# Moisture_Probe.net
KiCad netlist of a schematic drawn in EAGLE
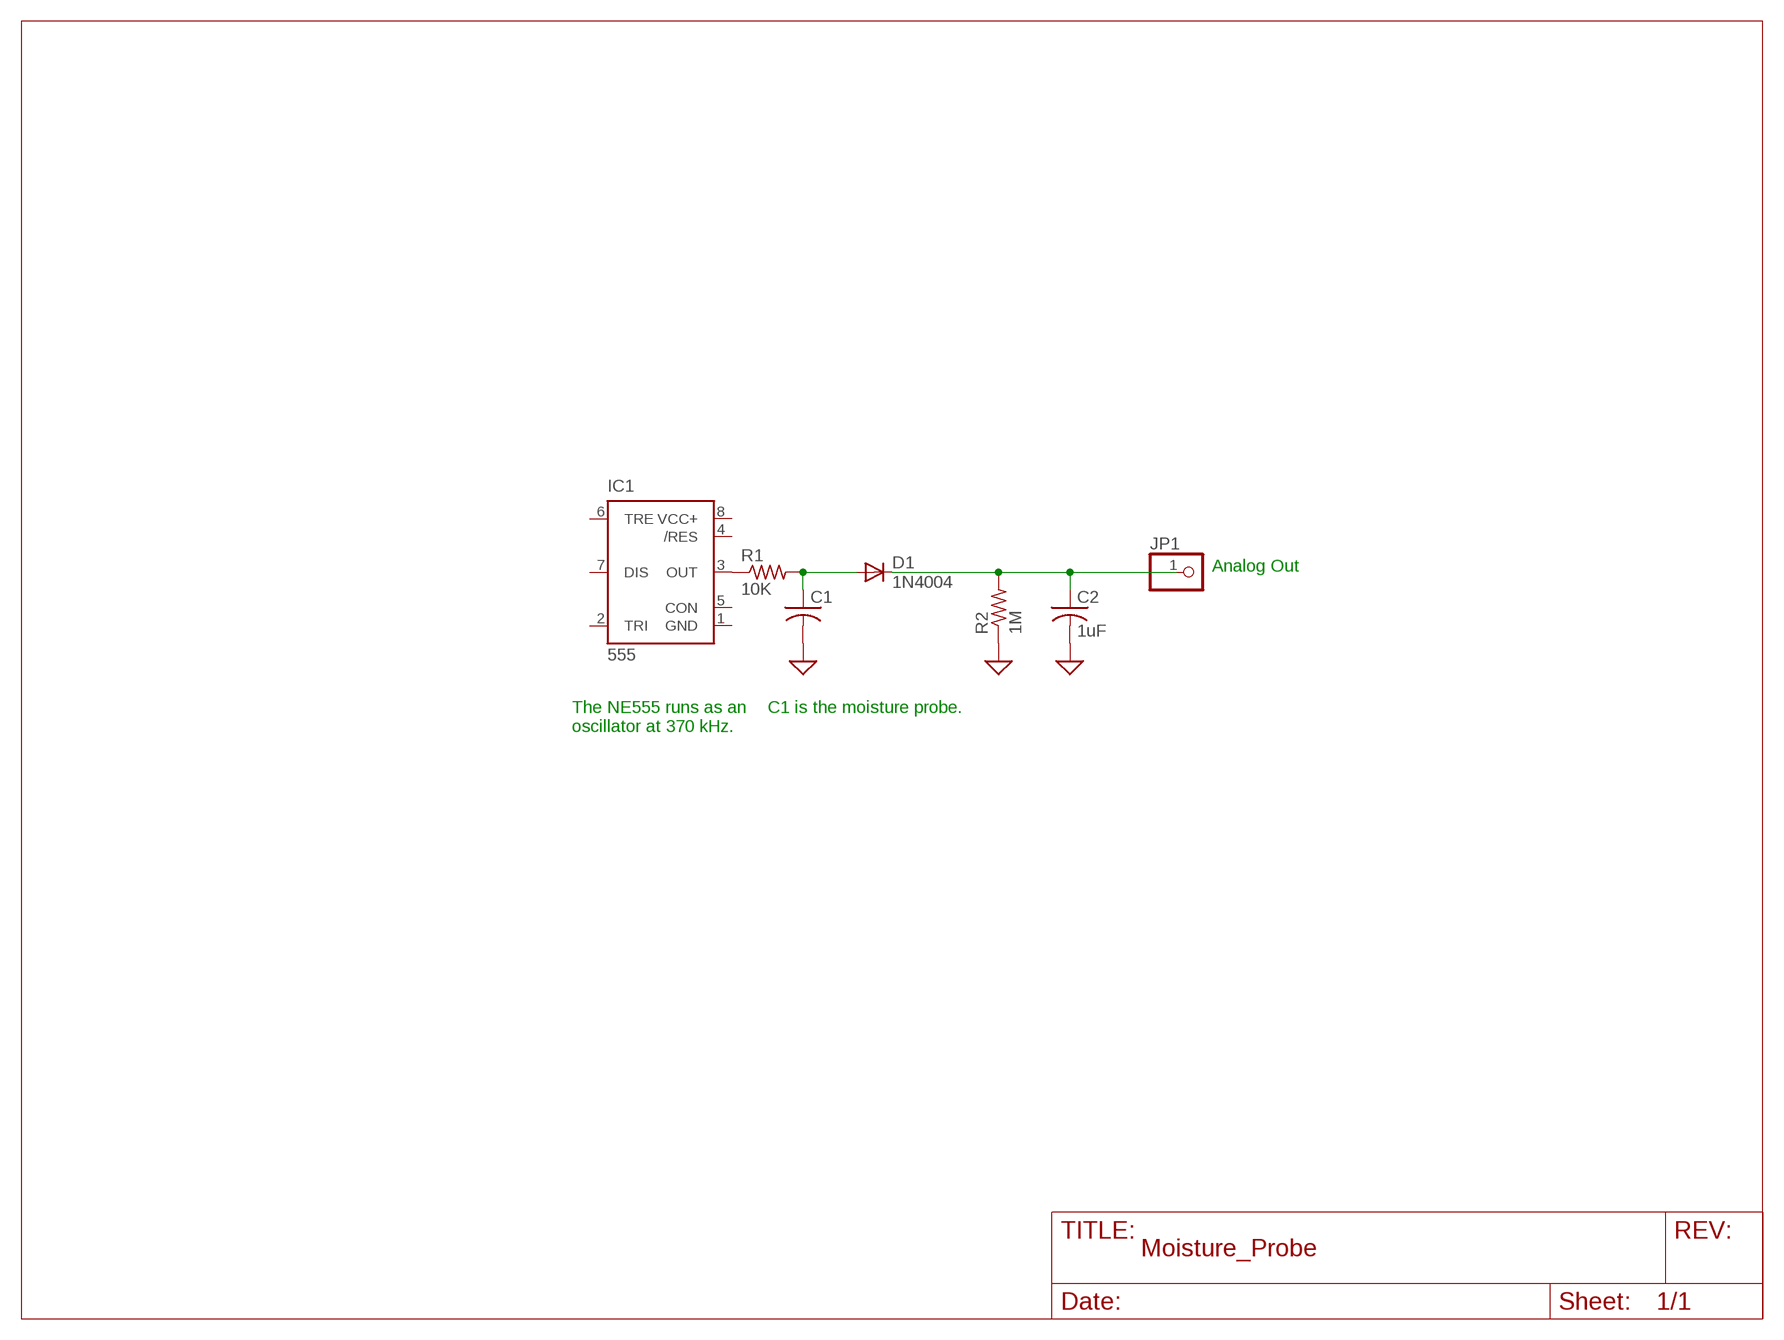
[diagram p0: schematic, sheet 1]

(export (version "E")
  (design (tool "Eeschema 10.0.6"))
  (components
    (comp (ref "C1")
      (value "C-US050-030X075")
      (footprint "eagle-import:C050-030X075")
      (libsource (lib "eagle-import") (part "C-US050-030X075"))
    )
    (comp (ref "C2")
      (value "1uF")
      (footprint "eagle-import:C050-030X075")
      (libsource (lib "eagle-import") (part "C-US050-030X075"))
    )
    (comp (ref "D1")
      (value "1N4004")
      (footprint "eagle-import:DO41-10")
      (libsource (lib "eagle-import") (part "1N4004"))
    )
    (comp (ref "IC1")
      (value "555")
      (footprint "eagle-import:DIP08")
      (libsource (lib "eagle-import") (part "555P"))
    )
    (comp (ref "JP1")
      (value "PINHD-1X1")
      (footprint "eagle-import:1X01")
      (libsource (lib "eagle-import") (part "PINHD-1X1"))
    )
    (comp (ref "R1")
      (value "10K")
      (footprint "eagle-import:0204_7")
      (libsource (lib "eagle-import") (part "R-US_0204/7"))
    )
    (comp (ref "R2")
      (value "1M")
      (footprint "eagle-import:0204_7")
      (libsource (lib "eagle-import") (part "R-US_0204/7"))
    )
  )
  (nets
    (net (code "1") (name "/GND") (class "Default")
      (node (ref "IC1") (pin "1") (pinfunction "GND_1") (pintype "power_in"))
    )
    (net (code "2") (name "/VCC+") (class "Default")
      (node (ref "IC1") (pin "8") (pinfunction "VCC+_8") (pintype "power_in"))
    )
    (net (code "3") (name "Net-(C1-Pad1)") (class "Default")
      (node (ref "C1") (pin "1") (pinfunction "1_1") (pintype "passive"))
      (node (ref "D1") (pin "A") (pinfunction "A_A") (pintype "passive"))
      (node (ref "R1") (pin "2") (pinfunction "2_2") (pintype "passive"))
    )
    (net (code "4") (name "Net-(C2-Pad1)") (class "Default")
      (node (ref "C2") (pin "1") (pinfunction "1_1") (pintype "passive"))
      (node (ref "D1") (pin "C") (pinfunction "C_C") (pintype "passive"))
      (node (ref "JP1") (pin "1") (pinfunction "1_1") (pintype "passive"))
      (node (ref "R2") (pin "2") (pinfunction "2_2") (pintype "passive"))
    )
    (net (code "5") (name "Net-(IC1-OUT)") (class "Default")
      (node (ref "IC1") (pin "3") (pinfunction "OUT_3") (pintype "output"))
      (node (ref "R1") (pin "1") (pinfunction "1_1") (pintype "passive"))
    )
    (net (code "6") (name "SUP") (class "Default")
      (node (ref "C1") (pin "2") (pinfunction "2_2") (pintype "passive"))
      (node (ref "C2") (pin "2") (pinfunction "2_2") (pintype "passive"))
      (node (ref "R2") (pin "1") (pinfunction "1_1") (pintype "passive"))
    )
    (net (code "7") (name "unconnected-(IC1-CON-Pad5)") (class "Default")
      (node (ref "IC1") (pin "5") (pinfunction "CON_5") (pintype "input"))
    )
    (net (code "8") (name "unconnected-(IC1-DIS-Pad7)") (class "Default")
      (node (ref "IC1") (pin "7") (pinfunction "DIS_7") (pintype "input"))
    )
    (net (code "9") (name "unconnected-(IC1-TRE-Pad6)") (class "Default")
      (node (ref "IC1") (pin "6") (pinfunction "TRE_6") (pintype "input"))
    )
    (net (code "10") (name "unconnected-(IC1-TRI-Pad2)") (class "Default")
      (node (ref "IC1") (pin "2") (pinfunction "TRI_2") (pintype "input"))
    )
    (net (code "11") (name "unconnected-(IC1-{slash}RES-Pad4)") (class "Default")
      (node (ref "IC1") (pin "4") (pinfunction "/RES_4") (pintype "input"))
    )
  )
)
